# Schematic.net
KiCad netlist of a schematic drawn in EasyEDA
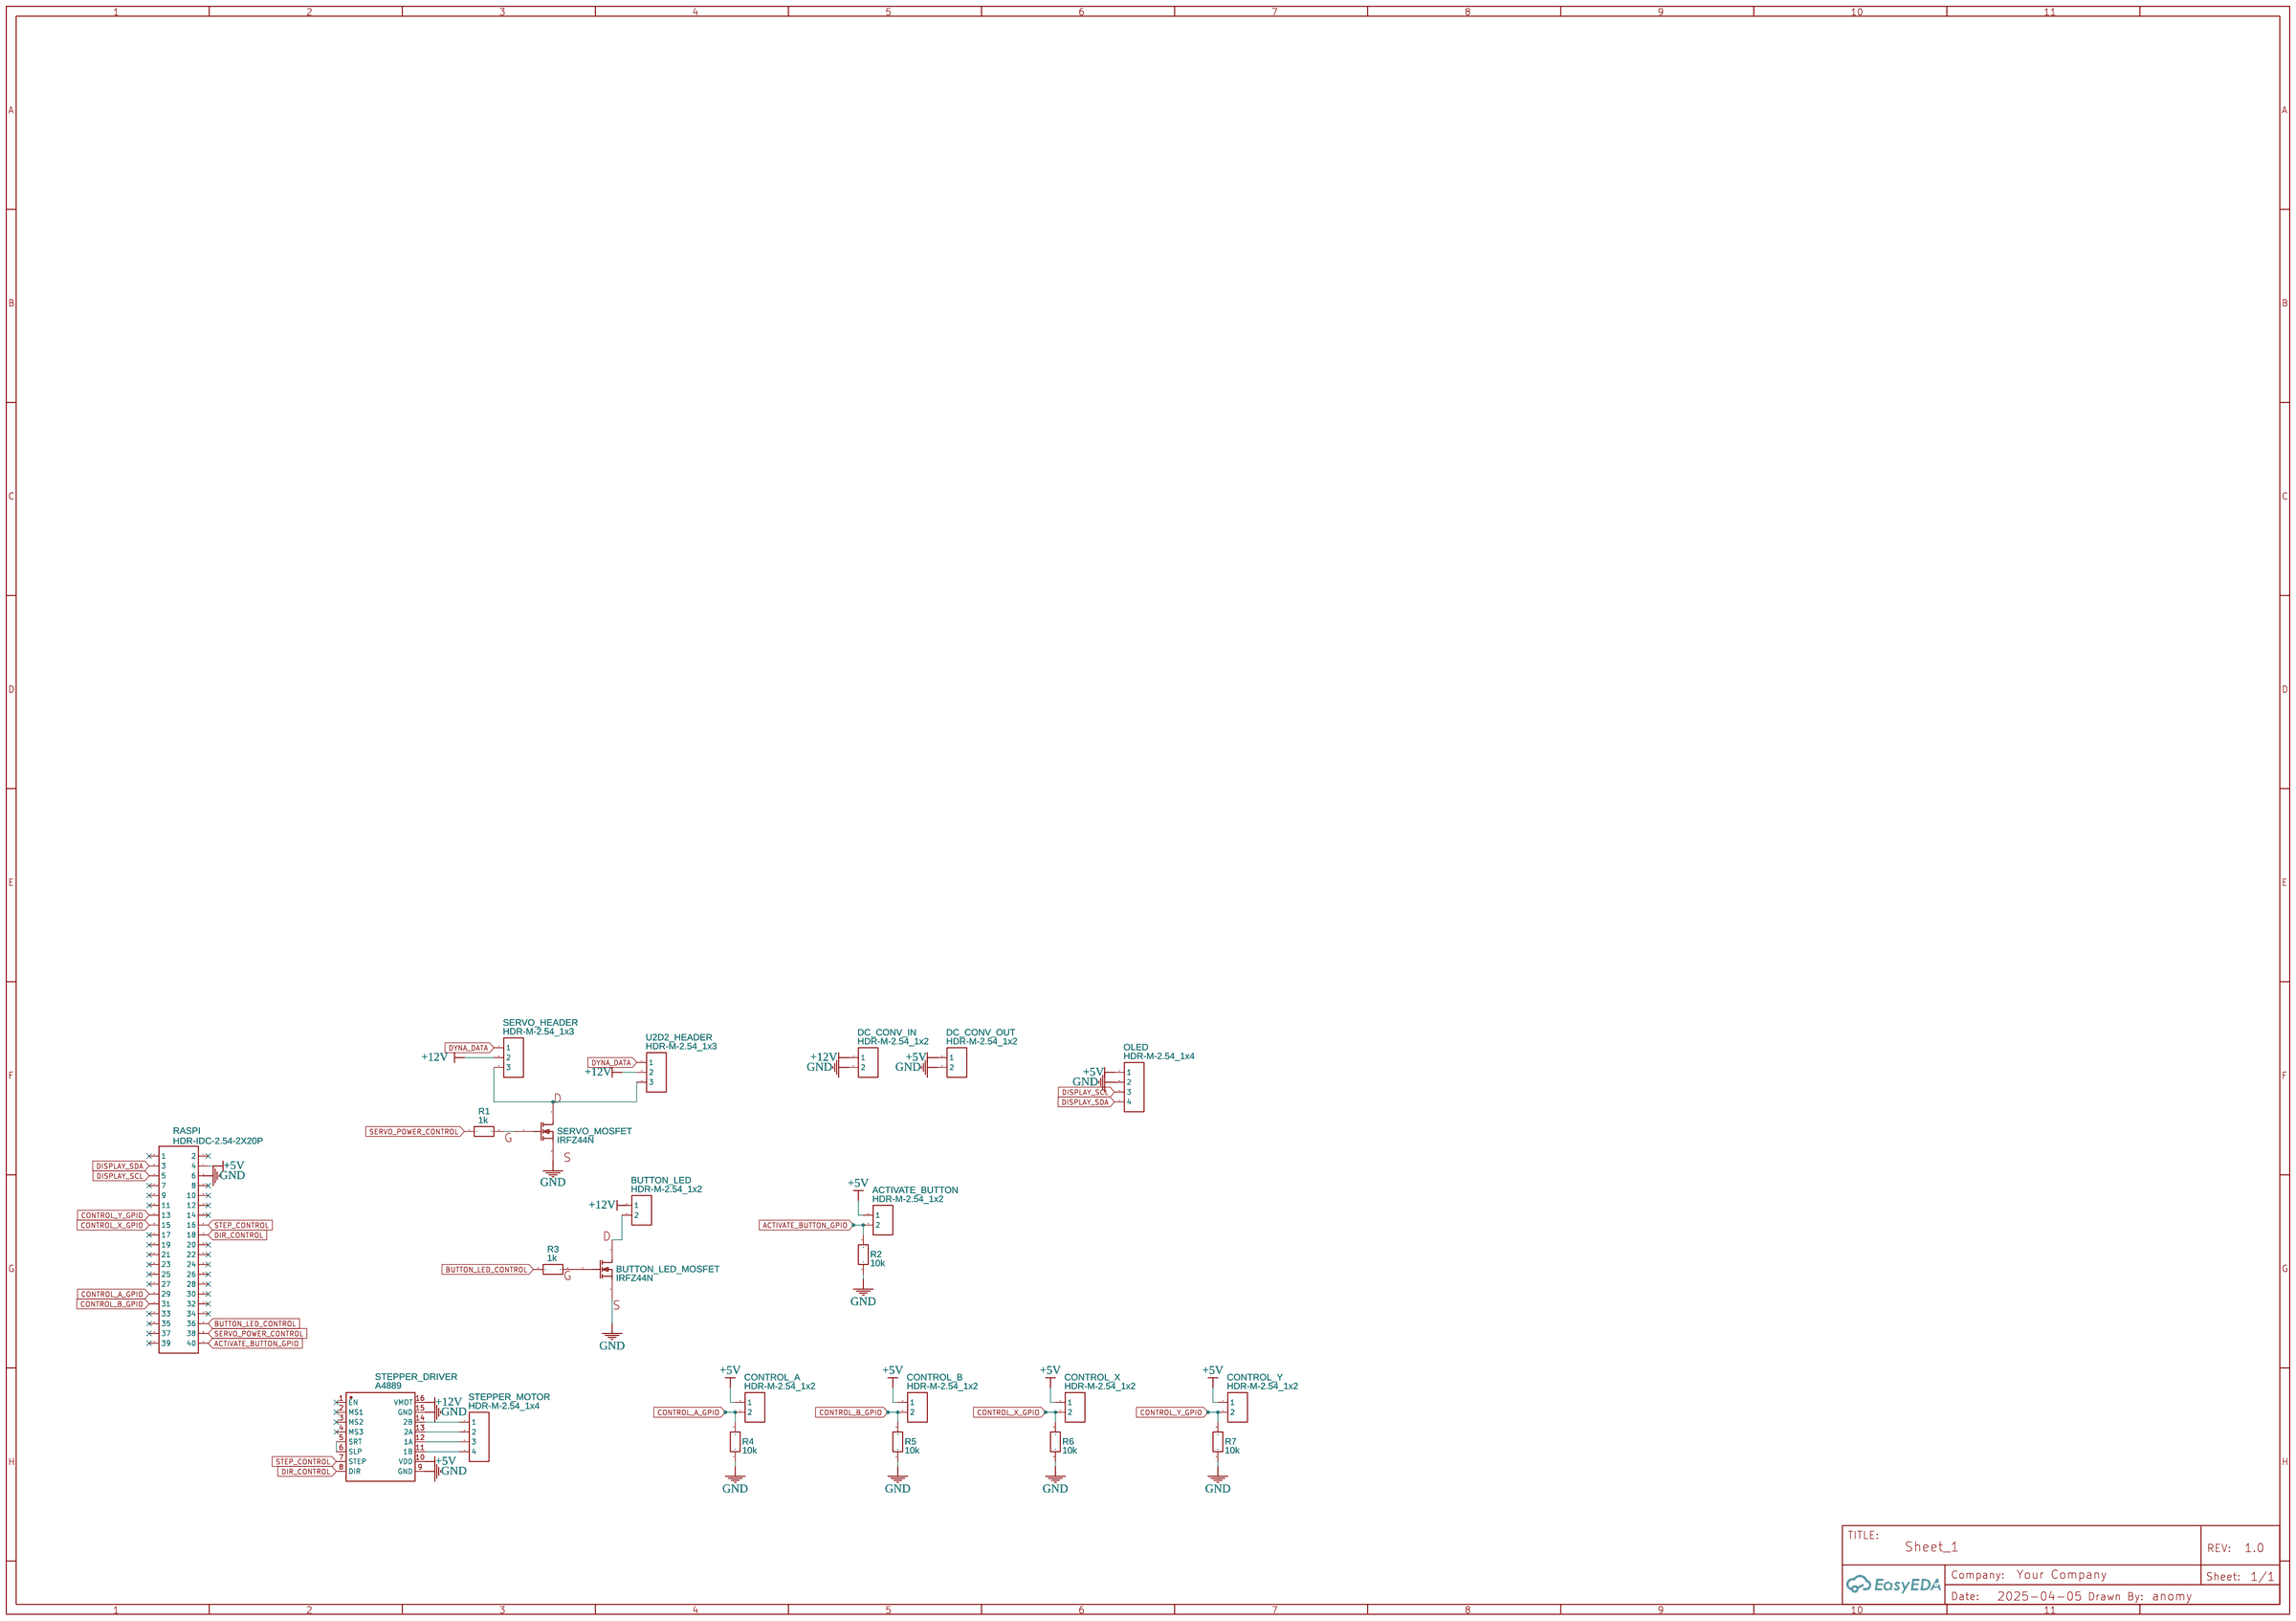
[diagram p0: schematic sheet]

(export (version "E")
  (design (tool "Eeschema 10.0.6"))
  (components
    (comp (ref "ACTIVATE_BUTTON") (value "HDR-M-2.54_1x2") (libsource (lib "") (part "HDR-M-2.54_1x2")))
    (comp (ref "BUTTON_LED") (value "HDR-M-2.54_1x2") (libsource (lib "") (part "HDR-M-2.54_1x2_2")))
    (comp (ref "BUTTON_LED_MOSFET") (value "IRFZ44N") (libsource (lib "") (part "IRFZ44N COPY_1")))
    (comp (ref "CONTROL_A") (value "HDR-M-2.54_1x2") (libsource (lib "") (part "HDR-M-2.54_1x2_4")))
    (comp (ref "CONTROL_B") (value "HDR-M-2.54_1x2") (libsource (lib "") (part "HDR-M-2.54_1x2_6")))
    (comp (ref "CONTROL_X") (value "HDR-M-2.54_1x2") (libsource (lib "") (part "HDR-M-2.54_1x2_5")))
    (comp (ref "CONTROL_Y") (value "HDR-M-2.54_1x2") (libsource (lib "") (part "HDR-M-2.54_1x2_3")))
    (comp (ref "DC_CONV_IN") (value "HDR-M-2.54_1x2") (libsource (lib "") (part "HDR-M-2.54_1x2_7")))
    (comp (ref "DC_CONV_OUT") (value "HDR-M-2.54_1x2") (libsource (lib "") (part "HDR-M-2.54_1x2_1")))
    (comp (ref "OLED") (value "HDR-M-2.54_1x4") (libsource (lib "") (part "HDR-M-2.54_1x4_1")))
    (comp (ref "R1") (value "1k") (libsource (lib "") (part "R_AXIAL-0.3_EU_1")))
    (comp (ref "R2") (value "10k") (libsource (lib "") (part "R_AXIAL-0.3_EU")))
    (comp (ref "R3") (value "1k") (libsource (lib "") (part "R_AXIAL-0.3_EU_1")))
    (comp (ref "R4") (value "10k") (libsource (lib "") (part "R_AXIAL-0.3_EU")))
    (comp (ref "R5") (value "10k") (libsource (lib "") (part "R_AXIAL-0.3_EU")))
    (comp (ref "R6") (value "10k") (libsource (lib "") (part "R_AXIAL-0.3_EU")))
    (comp (ref "R7") (value "10k") (libsource (lib "") (part "R_AXIAL-0.3_EU")))
    (comp (ref "RASPI")
      (value "HDR-IDC-2.54-2X20P")
      (fields
        (field (name "Manufacturer Part") "IDC Box 2X20 2.54MM")
        (field (name "Manufacturer") "BOOMELE")
      )
      (libsource (lib "") (part "HDR-IDC-2.54-2X20P"))
    )
    (comp (ref "SERVO_HEADER") (value "HDR-M-2.54_1x3") (libsource (lib "") (part "HDR-M-2.54_1x3_1")))
    (comp (ref "SERVO_MOSFET") (value "IRFZ44N") (libsource (lib "") (part "IRFZ44N COPY")))
    (comp (ref "STEPPER_DRIVER") (value "A4889") (libsource (lib "") (part "A4889")))
    (comp (ref "STEPPER_MOTOR") (value "HDR-M-2.54_1x4") (libsource (lib "") (part "HDR-M-2.54_1x4")))
    (comp (ref "U2D2_HEADER") (value "HDR-M-2.54_1x3") (libsource (lib "") (part "HDR-M-2.54_1x3")))
  )
  (nets
    (net (code "1") (name "+5V") (class "Default")
      (node (ref "ACTIVATE_BUTTON") (pin "1") (pinfunction "1_1") (pintype "unspecified"))
      (node (ref "CONTROL_A") (pin "1") (pinfunction "1_1") (pintype "unspecified"))
      (node (ref "CONTROL_B") (pin "1") (pinfunction "1_1") (pintype "unspecified"))
      (node (ref "CONTROL_X") (pin "1") (pinfunction "1_1") (pintype "unspecified"))
      (node (ref "CONTROL_Y") (pin "1") (pinfunction "1_1") (pintype "unspecified"))
      (node (ref "DC_CONV_OUT") (pin "1") (pinfunction "1_1") (pintype "unspecified"))
      (node (ref "OLED") (pin "1") (pinfunction "1_1") (pintype "unspecified"))
      (node (ref "RASPI") (pin "4") (pinfunction "4_4") (pintype "unspecified"))
      (node (ref "STEPPER_DRIVER") (pin "10") (pinfunction "VDD_10") (pintype "unspecified"))
    )
    (net (code "2") (name "+12V") (class "Default")
      (node (ref "BUTTON_LED") (pin "1") (pinfunction "1_1") (pintype "unspecified"))
      (node (ref "DC_CONV_IN") (pin "1") (pinfunction "1_1") (pintype "unspecified"))
      (node (ref "SERVO_HEADER") (pin "2") (pinfunction "2_2") (pintype "input"))
      (node (ref "STEPPER_DRIVER") (pin "16") (pinfunction "VMOT_16") (pintype "unspecified"))
      (node (ref "U2D2_HEADER") (pin "2") (pinfunction "2_2") (pintype "input"))
    )
    (net (code "3") (name "ACTIVATE_BUTTON_GPIO") (class "Default")
      (node (ref "ACTIVATE_BUTTON") (pin "2") (pinfunction "2_2") (pintype "unspecified"))
      (node (ref "R2") (pin "2") (pinfunction "2_2") (pintype "unspecified"))
      (node (ref "RASPI") (pin "40") (pinfunction "40_40") (pintype "unspecified"))
    )
    (net (code "4") (name "BUTTON_LED_CONTROL") (class "Default")
      (node (ref "R3") (pin "1") (pinfunction "1_1") (pintype "unspecified"))
      (node (ref "RASPI") (pin "36") (pinfunction "36_36") (pintype "unspecified"))
    )
    (net (code "5") (name "CONTROL_A_GPIO") (class "Default")
      (node (ref "CONTROL_A") (pin "2") (pinfunction "2_2") (pintype "unspecified"))
      (node (ref "R4") (pin "2") (pinfunction "2_2") (pintype "unspecified"))
      (node (ref "RASPI") (pin "29") (pinfunction "29_29") (pintype "unspecified"))
    )
    (net (code "6") (name "CONTROL_B_GPIO") (class "Default")
      (node (ref "CONTROL_B") (pin "2") (pinfunction "2_2") (pintype "unspecified"))
      (node (ref "R5") (pin "2") (pinfunction "2_2") (pintype "unspecified"))
      (node (ref "RASPI") (pin "31") (pinfunction "31_31") (pintype "unspecified"))
    )
    (net (code "7") (name "CONTROL_X_GPIO") (class "Default")
      (node (ref "CONTROL_X") (pin "2") (pinfunction "2_2") (pintype "unspecified"))
      (node (ref "R6") (pin "2") (pinfunction "2_2") (pintype "unspecified"))
      (node (ref "RASPI") (pin "15") (pinfunction "15_15") (pintype "unspecified"))
    )
    (net (code "8") (name "CONTROL_Y_GPIO") (class "Default")
      (node (ref "CONTROL_Y") (pin "2") (pinfunction "2_2") (pintype "unspecified"))
      (node (ref "R7") (pin "2") (pinfunction "2_2") (pintype "unspecified"))
      (node (ref "RASPI") (pin "13") (pinfunction "13_13") (pintype "unspecified"))
    )
    (net (code "9") (name "DIR_CONTROL") (class "Default")
      (node (ref "RASPI") (pin "18") (pinfunction "18_18") (pintype "unspecified"))
      (node (ref "STEPPER_DRIVER") (pin "8") (pinfunction "DIR_8") (pintype "unspecified"))
    )
    (net (code "10") (name "DISPLAY_SCL") (class "Default")
      (node (ref "OLED") (pin "3") (pinfunction "3_3") (pintype "unspecified"))
      (node (ref "RASPI") (pin "5") (pinfunction "5_5") (pintype "unspecified"))
    )
    (net (code "11") (name "DISPLAY_SDA") (class "Default")
      (node (ref "OLED") (pin "4") (pinfunction "4_4") (pintype "unspecified"))
      (node (ref "RASPI") (pin "3") (pinfunction "3_3") (pintype "unspecified"))
    )
    (net (code "12") (name "DYNA_DATA") (class "Default")
      (node (ref "SERVO_HEADER") (pin "1") (pinfunction "1_1") (pintype "input"))
      (node (ref "U2D2_HEADER") (pin "1") (pinfunction "1_1") (pintype "input"))
    )
    (net (code "13") (name "GND") (class "Default")
      (node (ref "BUTTON_LED_MOSFET") (pin "3") (pinfunction "S_3") (pintype "unspecified"))
      (node (ref "DC_CONV_IN") (pin "2") (pinfunction "2_2") (pintype "unspecified"))
      (node (ref "DC_CONV_OUT") (pin "2") (pinfunction "2_2") (pintype "unspecified"))
      (node (ref "OLED") (pin "2") (pinfunction "2_2") (pintype "unspecified"))
      (node (ref "R2") (pin "1") (pinfunction "1_1") (pintype "unspecified"))
      (node (ref "R4") (pin "1") (pinfunction "1_1") (pintype "unspecified"))
      (node (ref "R5") (pin "1") (pinfunction "1_1") (pintype "unspecified"))
      (node (ref "R6") (pin "1") (pinfunction "1_1") (pintype "unspecified"))
      (node (ref "R7") (pin "1") (pinfunction "1_1") (pintype "unspecified"))
      (node (ref "RASPI") (pin "6") (pinfunction "6_6") (pintype "passive"))
      (node (ref "SERVO_MOSFET") (pin "3") (pinfunction "S_3") (pintype "unspecified"))
      (node (ref "STEPPER_DRIVER") (pin "15") (pinfunction "GND_15") (pintype "unspecified"))
      (node (ref "STEPPER_DRIVER") (pin "9") (pinfunction "GND_9") (pintype "unspecified"))
    )
    (net (code "14") (name "Net-(BUTTON_LED_MOSFET-D)") (class "Default")
      (node (ref "BUTTON_LED") (pin "2") (pinfunction "2_2") (pintype "unspecified"))
      (node (ref "BUTTON_LED_MOSFET") (pin "2") (pinfunction "D_2") (pintype "unspecified"))
    )
    (net (code "15") (name "Net-(BUTTON_LED_MOSFET-G)") (class "Default")
      (node (ref "BUTTON_LED_MOSFET") (pin "1") (pinfunction "G_1") (pintype "unspecified"))
      (node (ref "R3") (pin "2") (pinfunction "2_2") (pintype "unspecified"))
    )
    (net (code "16") (name "Net-(SERVO_MOSFET-D)") (class "Default")
      (node (ref "SERVO_HEADER") (pin "3") (pinfunction "3_3") (pintype "input"))
      (node (ref "SERVO_MOSFET") (pin "2") (pinfunction "D_2") (pintype "unspecified"))
      (node (ref "U2D2_HEADER") (pin "3") (pinfunction "3_3") (pintype "input"))
    )
    (net (code "17") (name "Net-(SERVO_MOSFET-G)") (class "Default")
      (node (ref "R1") (pin "2") (pinfunction "2_2") (pintype "unspecified"))
      (node (ref "SERVO_MOSFET") (pin "1") (pinfunction "G_1") (pintype "unspecified"))
    )
    (net (code "18") (name "Net-(STEPPER_DRIVER-1A)") (class "Default")
      (node (ref "STEPPER_DRIVER") (pin "12") (pinfunction "1A_12") (pintype "unspecified"))
      (node (ref "STEPPER_MOTOR") (pin "3") (pinfunction "3_3") (pintype "unspecified"))
    )
    (net (code "19") (name "Net-(STEPPER_DRIVER-1B)") (class "Default")
      (node (ref "STEPPER_DRIVER") (pin "11") (pinfunction "1B_11") (pintype "unspecified"))
      (node (ref "STEPPER_MOTOR") (pin "4") (pinfunction "4_4") (pintype "unspecified"))
    )
    (net (code "20") (name "Net-(STEPPER_DRIVER-2A)") (class "Default")
      (node (ref "STEPPER_DRIVER") (pin "13") (pinfunction "2A_13") (pintype "unspecified"))
      (node (ref "STEPPER_MOTOR") (pin "2") (pinfunction "2_2") (pintype "unspecified"))
    )
    (net (code "21") (name "Net-(STEPPER_DRIVER-2B)") (class "Default")
      (node (ref "STEPPER_DRIVER") (pin "14") (pinfunction "2B_14") (pintype "unspecified"))
      (node (ref "STEPPER_MOTOR") (pin "1") (pinfunction "1_1") (pintype "unspecified"))
    )
    (net (code "22") (name "Net-(STEPPER_DRIVER-SLP)") (class "Default")
      (node (ref "STEPPER_DRIVER") (pin "5") (pinfunction "SRT_5") (pintype "unspecified"))
      (node (ref "STEPPER_DRIVER") (pin "6") (pinfunction "SLP_6") (pintype "unspecified"))
    )
    (net (code "23") (name "SERVO_POWER_CONTROL") (class "Default")
      (node (ref "R1") (pin "1") (pinfunction "1_1") (pintype "unspecified"))
      (node (ref "RASPI") (pin "38") (pinfunction "38_38") (pintype "unspecified"))
    )
    (net (code "24") (name "STEP_CONTROL") (class "Default")
      (node (ref "RASPI") (pin "16") (pinfunction "16_16") (pintype "unspecified"))
      (node (ref "STEPPER_DRIVER") (pin "7") (pinfunction "STEP_7") (pintype "unspecified"))
    )
    (net (code "25") (name "unconnected-(RASPI-Pad1)") (class "Default")
      (node (ref "RASPI") (pin "1") (pinfunction "1_1") (pintype "unspecified+no_connect"))
    )
    (net (code "26") (name "unconnected-(RASPI-Pad2)") (class "Default")
      (node (ref "RASPI") (pin "2") (pinfunction "2_2") (pintype "unspecified+no_connect"))
    )
    (net (code "27") (name "unconnected-(RASPI-Pad7)") (class "Default")
      (node (ref "RASPI") (pin "7") (pinfunction "7_7") (pintype "unspecified+no_connect"))
    )
    (net (code "28") (name "unconnected-(RASPI-Pad8)") (class "Default")
      (node (ref "RASPI") (pin "8") (pinfunction "8_8") (pintype "unspecified+no_connect"))
    )
    (net (code "29") (name "unconnected-(RASPI-Pad9)") (class "Default")
      (node (ref "RASPI") (pin "9") (pinfunction "9_9") (pintype "unspecified+no_connect"))
    )
    (net (code "30") (name "unconnected-(RASPI-Pad10)") (class "Default")
      (node (ref "RASPI") (pin "10") (pinfunction "10_10") (pintype "unspecified+no_connect"))
    )
    (net (code "31") (name "unconnected-(RASPI-Pad11)") (class "Default")
      (node (ref "RASPI") (pin "11") (pinfunction "11_11") (pintype "unspecified+no_connect"))
    )
    (net (code "32") (name "unconnected-(RASPI-Pad12)") (class "Default")
      (node (ref "RASPI") (pin "12") (pinfunction "12_12") (pintype "unspecified+no_connect"))
    )
    (net (code "33") (name "unconnected-(RASPI-Pad14)") (class "Default")
      (node (ref "RASPI") (pin "14") (pinfunction "14_14") (pintype "unspecified+no_connect"))
    )
    (net (code "34") (name "unconnected-(RASPI-Pad17)") (class "Default")
      (node (ref "RASPI") (pin "17") (pinfunction "17_17") (pintype "unspecified+no_connect"))
    )
    (net (code "35") (name "unconnected-(RASPI-Pad19)") (class "Default")
      (node (ref "RASPI") (pin "19") (pinfunction "19_19") (pintype "unspecified+no_connect"))
    )
    (net (code "36") (name "unconnected-(RASPI-Pad20)") (class "Default")
      (node (ref "RASPI") (pin "20") (pinfunction "20_20") (pintype "unspecified+no_connect"))
    )
    (net (code "37") (name "unconnected-(RASPI-Pad21)") (class "Default")
      (node (ref "RASPI") (pin "21") (pinfunction "21_21") (pintype "unspecified+no_connect"))
    )
    (net (code "38") (name "unconnected-(RASPI-Pad22)") (class "Default")
      (node (ref "RASPI") (pin "22") (pinfunction "22_22") (pintype "unspecified+no_connect"))
    )
    (net (code "39") (name "unconnected-(RASPI-Pad23)") (class "Default")
      (node (ref "RASPI") (pin "23") (pinfunction "23_23") (pintype "unspecified+no_connect"))
    )
    (net (code "40") (name "unconnected-(RASPI-Pad24)") (class "Default")
      (node (ref "RASPI") (pin "24") (pinfunction "24_24") (pintype "unspecified+no_connect"))
    )
    (net (code "41") (name "unconnected-(RASPI-Pad25)") (class "Default")
      (node (ref "RASPI") (pin "25") (pinfunction "25_25") (pintype "unspecified+no_connect"))
    )
    (net (code "42") (name "unconnected-(RASPI-Pad26)") (class "Default")
      (node (ref "RASPI") (pin "26") (pinfunction "26_26") (pintype "unspecified+no_connect"))
    )
    (net (code "43") (name "unconnected-(RASPI-Pad27)") (class "Default")
      (node (ref "RASPI") (pin "27") (pinfunction "27_27") (pintype "unspecified+no_connect"))
    )
    (net (code "44") (name "unconnected-(RASPI-Pad28)") (class "Default")
      (node (ref "RASPI") (pin "28") (pinfunction "28_28") (pintype "unspecified+no_connect"))
    )
    (net (code "45") (name "unconnected-(RASPI-Pad30)") (class "Default")
      (node (ref "RASPI") (pin "30") (pinfunction "30_30") (pintype "unspecified+no_connect"))
    )
    (net (code "46") (name "unconnected-(RASPI-Pad32)") (class "Default")
      (node (ref "RASPI") (pin "32") (pinfunction "32_32") (pintype "unspecified+no_connect"))
    )
    (net (code "47") (name "unconnected-(RASPI-Pad33)") (class "Default")
      (node (ref "RASPI") (pin "33") (pinfunction "33_33") (pintype "unspecified+no_connect"))
    )
    (net (code "48") (name "unconnected-(RASPI-Pad34)") (class "Default")
      (node (ref "RASPI") (pin "34") (pinfunction "34_34") (pintype "unspecified+no_connect"))
    )
    (net (code "49") (name "unconnected-(RASPI-Pad35)") (class "Default")
      (node (ref "RASPI") (pin "35") (pinfunction "35_35") (pintype "unspecified+no_connect"))
    )
    (net (code "50") (name "unconnected-(RASPI-Pad37)") (class "Default")
      (node (ref "RASPI") (pin "37") (pinfunction "37_37") (pintype "unspecified+no_connect"))
    )
    (net (code "51") (name "unconnected-(RASPI-Pad39)") (class "Default")
      (node (ref "RASPI") (pin "39") (pinfunction "39_39") (pintype "unspecified+no_connect"))
    )
    (net (code "52") (name "unconnected-(STEPPER_DRIVER-EN-Pad1)") (class "Default")
      (node (ref "STEPPER_DRIVER") (pin "1") (pinfunction "EN_1") (pintype "unspecified+no_connect"))
    )
    (net (code "53") (name "unconnected-(STEPPER_DRIVER-MS1-Pad2)") (class "Default")
      (node (ref "STEPPER_DRIVER") (pin "2") (pinfunction "MS1_2") (pintype "unspecified+no_connect"))
    )
    (net (code "54") (name "unconnected-(STEPPER_DRIVER-MS2-Pad3)") (class "Default")
      (node (ref "STEPPER_DRIVER") (pin "3") (pinfunction "MS2_3") (pintype "unspecified+no_connect"))
    )
    (net (code "55") (name "unconnected-(STEPPER_DRIVER-MS3-Pad4)") (class "Default")
      (node (ref "STEPPER_DRIVER") (pin "4") (pinfunction "MS3_4") (pintype "unspecified+no_connect"))
    )
  )
)
